# pcb-bldc-servo.net
KiCad netlist of a schematic drawn in EAGLE
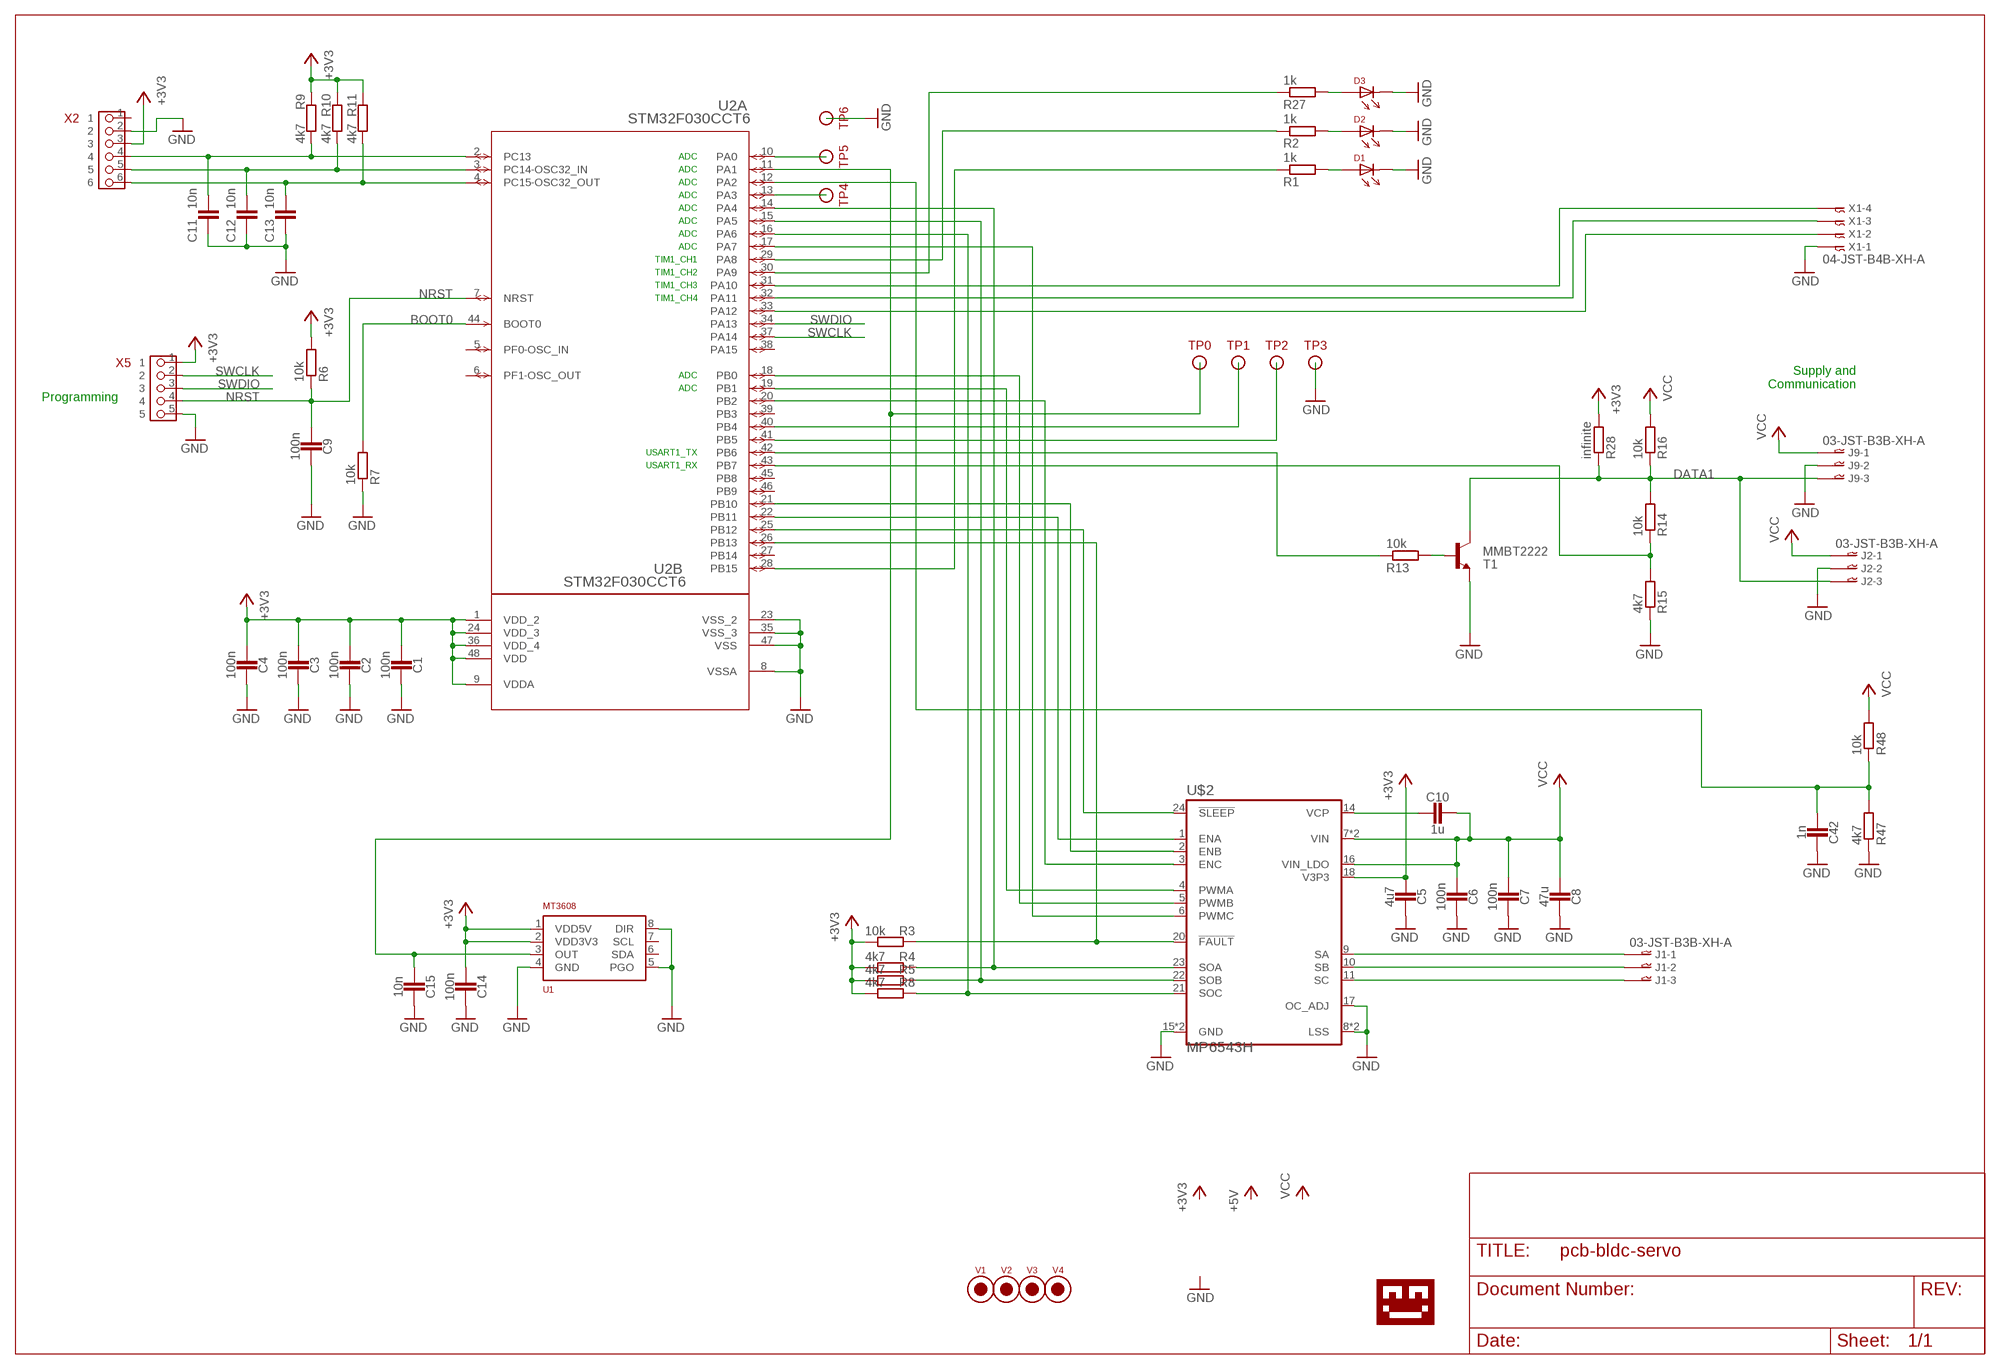
[diagram p0: schematic, sheet 1]

(export (version "E")
  (design (tool "Eeschema 10.0.6"))
  (components
    (comp (ref "C1")
      (value "100n")
      (footprint "eagle-import:0603_CAP")
      (libsource (lib "eagle-import") (part "CAPACITOR0603_CAP"))
    )
    (comp (ref "C2")
      (value "100n")
      (footprint "eagle-import:0603_CAP")
      (libsource (lib "eagle-import") (part "CAPACITOR0603_CAP"))
    )
    (comp (ref "C3")
      (value "100n")
      (footprint "eagle-import:0603_CAP")
      (libsource (lib "eagle-import") (part "CAPACITOR0603_CAP"))
    )
    (comp (ref "C4")
      (value "100n")
      (footprint "eagle-import:0603_CAP")
      (libsource (lib "eagle-import") (part "CAPACITOR0603_CAP"))
    )
    (comp (ref "C5")
      (value "4u7")
      (footprint "eagle-import:0805_CAP")
      (libsource (lib "eagle-import") (part "CAPACITOR0805_CAP"))
    )
    (comp (ref "C6")
      (value "100n")
      (footprint "eagle-import:0603_CAP")
      (libsource (lib "eagle-import") (part "CAPACITOR0603_CAP"))
    )
    (comp (ref "C7")
      (value "100n")
      (footprint "eagle-import:0603_CAP")
      (libsource (lib "eagle-import") (part "CAPACITOR0603_CAP"))
    )
    (comp (ref "C8")
      (value "47u")
      (footprint "eagle-import:1210_CAP")
      (libsource (lib "eagle-import") (part "CAPACITOR1210_CAP"))
    )
    (comp (ref "C9")
      (value "100n")
      (footprint "eagle-import:0603_CAP")
      (libsource (lib "eagle-import") (part "CAPACITOR0603_CAP"))
    )
    (comp (ref "C10")
      (value "1u")
      (footprint "eagle-import:0603_CAP")
      (libsource (lib "eagle-import") (part "CAPACITOR0603_CAP"))
    )
    (comp (ref "C11")
      (value "10n")
      (footprint "eagle-import:0603_CAP")
      (libsource (lib "eagle-import") (part "CAPACITOR0603_CAP"))
    )
    (comp (ref "C12")
      (value "10n")
      (footprint "eagle-import:0603_CAP")
      (libsource (lib "eagle-import") (part "CAPACITOR0603_CAP"))
    )
    (comp (ref "C13")
      (value "10n")
      (footprint "eagle-import:0603_CAP")
      (libsource (lib "eagle-import") (part "CAPACITOR0603_CAP"))
    )
    (comp (ref "C14")
      (value "100n")
      (footprint "eagle-import:0603_CAP")
      (libsource (lib "eagle-import") (part "CAPACITOR0603_CAP"))
    )
    (comp (ref "C15")
      (value "10n")
      (footprint "eagle-import:0603_CAP")
      (libsource (lib "eagle-import") (part "CAPACITOR0603_CAP"))
    )
    (comp (ref "C42")
      (value "1n")
      (footprint "eagle-import:0603_CAP")
      (libsource (lib "eagle-import") (part "CAPACITOR0603_CAP"))
    )
    (comp (ref "D1")
      (value "LED-0805")
      (footprint "eagle-import:0805-DOT")
      (libsource (lib "eagle-import") (part "LED-0805"))
    )
    (comp (ref "D2")
      (value "LED-0805")
      (footprint "eagle-import:0805-DOT")
      (libsource (lib "eagle-import") (part "LED-0805"))
    )
    (comp (ref "D3")
      (value "LED-0805")
      (footprint "eagle-import:0805-DOT")
      (libsource (lib "eagle-import") (part "LED-0805"))
    )
    (comp (ref "J1")
      (value "03-JST-B3B-XH-A")
      (footprint "eagle-import:B3B-XH")
      (libsource (lib "eagle-import") (part "03-JST-B3B-XH-A"))
    )
    (comp (ref "J2")
      (value "03-JST-B3B-XH-A")
      (footprint "eagle-import:B3B-XH")
      (libsource (lib "eagle-import") (part "03-JST-B3B-XH-A"))
    )
    (comp (ref "J9")
      (value "03-JST-B3B-XH-A")
      (footprint "eagle-import:B3B-XH")
      (libsource (lib "eagle-import") (part "03-JST-B3B-XH-A"))
    )
    (comp (ref "R1")
      (value "1k")
      (footprint "eagle-import:0603-RES")
      (libsource (lib "eagle-import") (part "RESISTOR0603_RES"))
    )
    (comp (ref "R2")
      (value "1k")
      (footprint "eagle-import:0603-RES")
      (libsource (lib "eagle-import") (part "RESISTOR0603_RES"))
    )
    (comp (ref "R3")
      (value "10k")
      (footprint "eagle-import:0603-RES")
      (libsource (lib "eagle-import") (part "RESISTOR0603_RES"))
    )
    (comp (ref "R4")
      (value "4k7")
      (footprint "eagle-import:0603-RES")
      (libsource (lib "eagle-import") (part "RESISTOR0603_RES"))
    )
    (comp (ref "R5")
      (value "4k7")
      (footprint "eagle-import:0603-RES")
      (libsource (lib "eagle-import") (part "RESISTOR0603_RES"))
    )
    (comp (ref "R6")
      (value "10k")
      (footprint "eagle-import:0603-RES")
      (libsource (lib "eagle-import") (part "RESISTOR0603_RES"))
    )
    (comp (ref "R7")
      (value "10k")
      (footprint "eagle-import:0603-RES")
      (libsource (lib "eagle-import") (part "RESISTOR0603_RES"))
    )
    (comp (ref "R8")
      (value "4k7")
      (footprint "eagle-import:0603-RES")
      (libsource (lib "eagle-import") (part "RESISTOR0603_RES"))
    )
    (comp (ref "R9")
      (value "4k7")
      (footprint "eagle-import:0603-RES")
      (libsource (lib "eagle-import") (part "RESISTOR0603_RES"))
    )
    (comp (ref "R10")
      (value "4k7")
      (footprint "eagle-import:0603-RES")
      (libsource (lib "eagle-import") (part "RESISTOR0603_RES"))
    )
    (comp (ref "R11")
      (value "4k7")
      (footprint "eagle-import:0603-RES")
      (libsource (lib "eagle-import") (part "RESISTOR0603_RES"))
    )
    (comp (ref "R13")
      (value "10k")
      (footprint "eagle-import:0603-RES")
      (libsource (lib "eagle-import") (part "RESISTOR0603_RES"))
    )
    (comp (ref "R14")
      (value "10k")
      (footprint "eagle-import:0603-RES")
      (libsource (lib "eagle-import") (part "RESISTOR0603_RES"))
    )
    (comp (ref "R15")
      (value "4k7")
      (footprint "eagle-import:0603-RES")
      (libsource (lib "eagle-import") (part "RESISTOR0603_RES"))
    )
    (comp (ref "R16")
      (value "10k")
      (footprint "eagle-import:0603-RES")
      (libsource (lib "eagle-import") (part "RESISTOR0603_RES"))
    )
    (comp (ref "R27")
      (value "1k")
      (footprint "eagle-import:0603-RES")
      (libsource (lib "eagle-import") (part "RESISTOR0603_RES"))
    )
    (comp (ref "R28")
      (value "infinite")
      (footprint "eagle-import:0603-RES")
      (libsource (lib "eagle-import") (part "RESISTOR0603_RES"))
    )
    (comp (ref "R47")
      (value "4k7")
      (footprint "eagle-import:0603-RES")
      (libsource (lib "eagle-import") (part "RESISTOR0603_RES"))
    )
    (comp (ref "R48")
      (value "10k")
      (footprint "eagle-import:0603-RES")
      (libsource (lib "eagle-import") (part "RESISTOR0603_RES"))
    )
    (comp (ref "T1")
      (value "MMBT2222")
      (footprint "eagle-import:SOT23-BEC")
      (libsource (lib "eagle-import") (part "-NPN-SOT23-BECMMBT2222ALT1"))
    )
    (comp (ref "TP0")
      (value "TESTPIN")
      (footprint "eagle-import:PIN-SMD-1X1-TEST_1M5")
      (libsource (lib "eagle-import") (part "TESTPIN"))
    )
    (comp (ref "TP1")
      (value "TESTPIN")
      (footprint "eagle-import:PIN-SMD-1X1-TEST_1M5")
      (libsource (lib "eagle-import") (part "TESTPIN"))
    )
    (comp (ref "TP2")
      (value "TESTPIN")
      (footprint "eagle-import:PIN-SMD-1X1-TEST_1M5")
      (libsource (lib "eagle-import") (part "TESTPIN"))
    )
    (comp (ref "TP3")
      (value "TESTPIN")
      (footprint "eagle-import:PIN-SMD-1X1-TEST_1M5")
      (libsource (lib "eagle-import") (part "TESTPIN"))
    )
    (comp (ref "TP4")
      (value "TESTPIN")
      (footprint "eagle-import:PIN-SMD-1X1-TEST_1M5")
      (libsource (lib "eagle-import") (part "TESTPIN"))
    )
    (comp (ref "TP5")
      (value "TESTPIN")
      (footprint "eagle-import:PIN-SMD-1X1-TEST_1M5")
      (libsource (lib "eagle-import") (part "TESTPIN"))
    )
    (comp (ref "TP6")
      (value "TESTPIN")
      (footprint "eagle-import:PIN-SMD-1X1-TEST_1M5")
      (libsource (lib "eagle-import") (part "TESTPIN"))
    )
    (comp (ref "U$1")
      (value "LOGO-TOBENG-1MM-FINISH")
      (footprint "eagle-import:TOBENG-1MM-FINISH")
      (libsource (lib "eagle-import") (part "LOGO-TOBENG-1MM-FINISH"))
    )
    (comp (ref "U$2")
      (value "MP6543H")
      (footprint "eagle-import:QFN24")
      (libsource (lib "eagle-import") (part "MP6543H"))
    )
    (comp (ref "U1")
      (value "AS5600")
      (footprint "eagle-import:SOIC-8")
      (libsource (lib "eagle-import") (part "AS5600"))
    )
    (comp (ref "U2")
      (value "STM32F030CCT6")
      (footprint "eagle-import:LQFP48-7X7MM")
      (fields (field (name "COPYRIGHT") "Copyright (C) 2018 Accelerated Designs. All rights reserved"))
      (libsource (lib "eagle-import") (part "STM32F030CCT6"))
    )
    (comp (ref "V1")
      (value "FIDUCIAL2MM")
      (footprint "eagle-import:FIDUCIAL_2MM")
      (libsource (lib "eagle-import") (part "FIDUCIAL2MM"))
    )
    (comp (ref "V2")
      (value "FIDUCIAL2MM")
      (footprint "eagle-import:FIDUCIAL_2MM")
      (libsource (lib "eagle-import") (part "FIDUCIAL2MM"))
    )
    (comp (ref "V3")
      (value "FIDUCIAL2MM")
      (footprint "eagle-import:FIDUCIAL_2MM")
      (libsource (lib "eagle-import") (part "FIDUCIAL2MM"))
    )
    (comp (ref "V4")
      (value "FIDUCIAL2MM")
      (footprint "eagle-import:FIDUCIAL_2MM")
      (libsource (lib "eagle-import") (part "FIDUCIAL2MM"))
    )
    (comp (ref "X1")
      (value "04-JST-B4B-XH-A")
      (footprint "eagle-import:B4B-XH")
      (libsource (lib "eagle-import") (part "04-JST-B4B-XH-A"))
    )
    (comp (ref "X2")
      (value "PIN_6X1")
      (footprint "eagle-import:PIN_6X1_MOLEX_PICOBLADE")
      (libsource (lib "eagle-import") (part "PIN_6X1"))
    )
    (comp (ref "X5")
      (value "PIN_5X1HD")
      (footprint "eagle-import:PIN_5X1_HD")
      (libsource (lib "eagle-import") (part "PIN_5X1HD"))
    )
  )
  (nets
    (net (code "1") (name "+3V3") (class "Default")
      (node (ref "C1") (pin "1") (pinfunction "1_1") (pintype "bidirectional"))
      (node (ref "C14") (pin "1") (pinfunction "1_1") (pintype "bidirectional"))
      (node (ref "C2") (pin "1") (pinfunction "1_1") (pintype "bidirectional"))
      (node (ref "C3") (pin "1") (pinfunction "1_1") (pintype "bidirectional"))
      (node (ref "C4") (pin "1") (pinfunction "1_1") (pintype "bidirectional"))
      (node (ref "C5") (pin "P$1") (pinfunction "1_P$1") (pintype "bidirectional"))
      (node (ref "R10") (pin "1") (pinfunction "1_1") (pintype "passive"))
      (node (ref "R11") (pin "1") (pinfunction "1_1") (pintype "passive"))
      (node (ref "R28") (pin "2") (pinfunction "2_2") (pintype "passive"))
      (node (ref "R3") (pin "2") (pinfunction "2_2") (pintype "passive"))
      (node (ref "R4") (pin "2") (pinfunction "2_2") (pintype "passive"))
      (node (ref "R5") (pin "2") (pinfunction "2_2") (pintype "passive"))
      (node (ref "R6") (pin "2") (pinfunction "2_2") (pintype "passive"))
      (node (ref "R8") (pin "2") (pinfunction "2_2") (pintype "passive"))
      (node (ref "R9") (pin "1") (pinfunction "1_1") (pintype "passive"))
      (node (ref "U$2") (pin "18") (pinfunction "V3P3_18") (pintype "bidirectional"))
      (node (ref "U1") (pin "1") (pinfunction "VDD5V_1") (pintype "bidirectional"))
      (node (ref "U1") (pin "2") (pinfunction "VDD3V3_2") (pintype "bidirectional"))
      (node (ref "U2") (pin "1") (pinfunction "VDD_2_1") (pintype "power_in"))
      (node (ref "U2") (pin "24") (pinfunction "VDD_3_24") (pintype "power_in"))
      (node (ref "U2") (pin "36") (pinfunction "VDD_4_36") (pintype "power_in"))
      (node (ref "U2") (pin "48") (pinfunction "VDD_48") (pintype "power_in"))
      (node (ref "U2") (pin "9") (pinfunction "VDDA_9") (pintype "power_in"))
      (node (ref "X2") (pin "3") (pinfunction "3_3") (pintype "bidirectional"))
      (node (ref "X5") (pin "1") (pinfunction "1_1") (pintype "bidirectional"))
    )
    (net (code "3") (name "/BOOT0") (class "Default")
      (node (ref "R7") (pin "2") (pinfunction "2_2") (pintype "passive"))
      (node (ref "U2") (pin "44") (pinfunction "BOOT0_44") (pintype "input"))
    )
    (net (code "4") (name "/DATA1") (class "Default")
      (node (ref "J2") (pin "P$3") (pinfunction "1_P$3") (pintype "passive"))
      (node (ref "J9") (pin "P$3") (pinfunction "1_P$3") (pintype "passive"))
      (node (ref "R14") (pin "2") (pinfunction "2_2") (pintype "passive"))
      (node (ref "R16") (pin "1") (pinfunction "1_1") (pintype "passive"))
      (node (ref "R28") (pin "1") (pinfunction "1_1") (pintype "passive"))
      (node (ref "T1") (pin "C") (pinfunction "C_C") (pintype "passive"))
    )
    (net (code "5") (name "/NRST") (class "Default")
      (node (ref "C9") (pin "1") (pinfunction "1_1") (pintype "bidirectional"))
      (node (ref "R6") (pin "1") (pinfunction "1_1") (pintype "passive"))
      (node (ref "U2") (pin "7") (pinfunction "NRST_7") (pintype "bidirectional"))
      (node (ref "X5") (pin "4") (pinfunction "4_4") (pintype "bidirectional"))
    )
    (net (code "6") (name "/SWCLK") (class "Default")
      (node (ref "U2") (pin "37") (pinfunction "PA14_37") (pintype "bidirectional"))
      (node (ref "X5") (pin "2") (pinfunction "2_2") (pintype "bidirectional"))
    )
    (net (code "7") (name "/SWDIO") (class "Default")
      (node (ref "U2") (pin "34") (pinfunction "PA13_34") (pintype "bidirectional"))
      (node (ref "X5") (pin "3") (pinfunction "3_3") (pintype "bidirectional"))
    )
    (net (code "8") (name "GND") (class "Default")
      (node (ref "C1") (pin "2") (pinfunction "2_2") (pintype "bidirectional"))
      (node (ref "C11") (pin "2") (pinfunction "2_2") (pintype "bidirectional"))
      (node (ref "C12") (pin "2") (pinfunction "2_2") (pintype "bidirectional"))
      (node (ref "C13") (pin "2") (pinfunction "2_2") (pintype "bidirectional"))
      (node (ref "C14") (pin "2") (pinfunction "2_2") (pintype "bidirectional"))
      (node (ref "C15") (pin "2") (pinfunction "2_2") (pintype "bidirectional"))
      (node (ref "C2") (pin "2") (pinfunction "2_2") (pintype "bidirectional"))
      (node (ref "C3") (pin "2") (pinfunction "2_2") (pintype "bidirectional"))
      (node (ref "C4") (pin "2") (pinfunction "2_2") (pintype "bidirectional"))
      (node (ref "C42") (pin "2") (pinfunction "2_2") (pintype "bidirectional"))
      (node (ref "C5") (pin "P$2") (pinfunction "2_P$2") (pintype "bidirectional"))
      (node (ref "C6") (pin "2") (pinfunction "2_2") (pintype "bidirectional"))
      (node (ref "C7") (pin "2") (pinfunction "2_2") (pintype "bidirectional"))
      (node (ref "C8") (pin "2") (pinfunction "2_2") (pintype "bidirectional"))
      (node (ref "C9") (pin "2") (pinfunction "2_2") (pintype "bidirectional"))
      (node (ref "D1") (pin "2") (pinfunction "2_2") (pintype "bidirectional"))
      (node (ref "D2") (pin "2") (pinfunction "2_2") (pintype "bidirectional"))
      (node (ref "D3") (pin "2") (pinfunction "2_2") (pintype "bidirectional"))
      (node (ref "J2") (pin "P$2") (pinfunction "1_P$2") (pintype "passive"))
      (node (ref "J9") (pin "P$2") (pinfunction "1_P$2") (pintype "passive"))
      (node (ref "R15") (pin "1") (pinfunction "1_1") (pintype "passive"))
      (node (ref "R47") (pin "1") (pinfunction "1_1") (pintype "passive"))
      (node (ref "R7") (pin "1") (pinfunction "1_1") (pintype "passive"))
      (node (ref "T1") (pin "E") (pinfunction "E_E") (pintype "passive"))
      (node (ref "TP3") (pin "1") (pinfunction "1_1") (pintype "bidirectional"))
      (node (ref "TP6") (pin "1") (pinfunction "1_1") (pintype "bidirectional"))
      (node (ref "U$2") (pin "12") (pinfunction "LSS_12") (pintype "bidirectional"))
      (node (ref "U$2") (pin "15") (pinfunction "GND_15") (pintype "bidirectional"))
      (node (ref "U$2") (pin "17") (pinfunction "OC_ADJ_17") (pintype "bidirectional"))
      (node (ref "U$2") (pin "25") (pinfunction "GND_25") (pintype "bidirectional"))
      (node (ref "U$2") (pin "8") (pinfunction "LSS_8") (pintype "bidirectional"))
      (node (ref "U1") (pin "4") (pinfunction "GND_4") (pintype "bidirectional"))
      (node (ref "U1") (pin "5") (pinfunction "PGO_5") (pintype "bidirectional"))
      (node (ref "U1") (pin "8") (pinfunction "DIR_8") (pintype "bidirectional"))
      (node (ref "U2") (pin "23") (pinfunction "VSS_2_23") (pintype "power_in"))
      (node (ref "U2") (pin "35") (pinfunction "VSS_3_35") (pintype "power_in"))
      (node (ref "U2") (pin "47") (pinfunction "VSS_47") (pintype "power_in"))
      (node (ref "U2") (pin "8") (pinfunction "VSSA_8") (pintype "power_in"))
      (node (ref "X1") (pin "P$1") (pinfunction "1_P$1") (pintype "passive"))
      (node (ref "X2") (pin "2") (pinfunction "2_2") (pintype "bidirectional"))
      (node (ref "X5") (pin "5") (pinfunction "5_5") (pintype "bidirectional"))
    )
    (net (code "9") (name "Net-(D1-Pad1)") (class "Default")
      (node (ref "D1") (pin "1") (pinfunction "1_1") (pintype "bidirectional"))
      (node (ref "R1") (pin "2") (pinfunction "2_2") (pintype "passive"))
    )
    (net (code "10") (name "Net-(D2-Pad1)") (class "Default")
      (node (ref "D2") (pin "1") (pinfunction "1_1") (pintype "bidirectional"))
      (node (ref "R2") (pin "2") (pinfunction "2_2") (pintype "passive"))
    )
    (net (code "11") (name "Net-(D3-Pad1)") (class "Default")
      (node (ref "D3") (pin "1") (pinfunction "1_1") (pintype "bidirectional"))
      (node (ref "R27") (pin "2") (pinfunction "2_2") (pintype "passive"))
    )
    (net (code "12") (name "Net-(J1A-1)") (class "Default")
      (node (ref "J1") (pin "P$1") (pinfunction "1_P$1") (pintype "passive"))
      (node (ref "U$2") (pin "9") (pinfunction "SA_9") (pintype "bidirectional"))
    )
    (net (code "13") (name "Net-(J1B-1)") (class "Default")
      (node (ref "J1") (pin "P$2") (pinfunction "1_P$2") (pintype "passive"))
      (node (ref "U$2") (pin "10") (pinfunction "SB_10") (pintype "bidirectional"))
    )
    (net (code "14") (name "Net-(J1C-1)") (class "Default")
      (node (ref "J1") (pin "P$3") (pinfunction "1_P$3") (pintype "passive"))
      (node (ref "U$2") (pin "11") (pinfunction "SC_11") (pintype "bidirectional"))
    )
    (net (code "15") (name "Net-(R13-Pad2)") (class "Default")
      (node (ref "R13") (pin "2") (pinfunction "2_2") (pintype "passive"))
      (node (ref "T1") (pin "B") (pinfunction "B_B") (pintype "passive"))
    )
    (net (code "16") (name "Net-(U$2-ENA)") (class "Default")
      (node (ref "U$2") (pin "1") (pinfunction "ENA_1") (pintype "bidirectional"))
      (node (ref "U2") (pin "22") (pinfunction "PB11_22") (pintype "bidirectional"))
    )
    (net (code "17") (name "Net-(U$2-ENB)") (class "Default")
      (node (ref "U$2") (pin "2") (pinfunction "ENB_2") (pintype "bidirectional"))
      (node (ref "U2") (pin "21") (pinfunction "PB10_21") (pintype "bidirectional"))
    )
    (net (code "18") (name "Net-(U$2-ENC)") (class "Default")
      (node (ref "U$2") (pin "3") (pinfunction "ENC_3") (pintype "bidirectional"))
      (node (ref "U2") (pin "20") (pinfunction "PB2_20") (pintype "bidirectional"))
    )
    (net (code "19") (name "Net-(U$2-PWMA)") (class "Default")
      (node (ref "U$2") (pin "4") (pinfunction "PWMA_4") (pintype "bidirectional"))
      (node (ref "U2") (pin "19") (pinfunction "PB1_19") (pintype "bidirectional"))
    )
    (net (code "20") (name "Net-(U$2-PWMB)") (class "Default")
      (node (ref "U$2") (pin "5") (pinfunction "PWMB_5") (pintype "bidirectional"))
      (node (ref "U2") (pin "18") (pinfunction "PB0_18") (pintype "bidirectional"))
    )
    (net (code "21") (name "Net-(U$2-PWMC)") (class "Default")
      (node (ref "U$2") (pin "6") (pinfunction "PWMC_6") (pintype "bidirectional"))
      (node (ref "U2") (pin "17") (pinfunction "PA7_17") (pintype "bidirectional"))
    )
    (net (code "22") (name "Net-(U$2-SOA)") (class "Default")
      (node (ref "R4") (pin "1") (pinfunction "1_1") (pintype "passive"))
      (node (ref "U$2") (pin "23") (pinfunction "SOA_23") (pintype "bidirectional"))
      (node (ref "U2") (pin "14") (pinfunction "PA4_14") (pintype "bidirectional"))
    )
    (net (code "23") (name "Net-(U$2-SOB)") (class "Default")
      (node (ref "R5") (pin "1") (pinfunction "1_1") (pintype "passive"))
      (node (ref "U$2") (pin "22") (pinfunction "SOB_22") (pintype "bidirectional"))
      (node (ref "U2") (pin "15") (pinfunction "PA5_15") (pintype "bidirectional"))
    )
    (net (code "24") (name "Net-(U$2-SOC)") (class "Default")
      (node (ref "R8") (pin "1") (pinfunction "1_1") (pintype "passive"))
      (node (ref "U$2") (pin "21") (pinfunction "SOC_21") (pintype "bidirectional"))
      (node (ref "U2") (pin "16") (pinfunction "PA6_16") (pintype "bidirectional"))
    )
    (net (code "25") (name "Net-(U$2-VCP)") (class "Default")
      (node (ref "C10") (pin "1") (pinfunction "1_1") (pintype "bidirectional"))
      (node (ref "U$2") (pin "14") (pinfunction "VCP_14") (pintype "bidirectional"))
    )
    (net (code "26") (name "Net-(U$2-~{FAULT})") (class "Default")
      (node (ref "R3") (pin "1") (pinfunction "1_1") (pintype "passive"))
      (node (ref "U$2") (pin "20") (pinfunction "~{FAULT}_20") (pintype "bidirectional"))
      (node (ref "U2") (pin "26") (pinfunction "PB13_26") (pintype "bidirectional"))
    )
    (net (code "27") (name "Net-(U$2-~{SLEEP})") (class "Default")
      (node (ref "U$2") (pin "24") (pinfunction "~{SLEEP}_24") (pintype "bidirectional"))
      (node (ref "U2") (pin "25") (pinfunction "PB12_25") (pintype "bidirectional"))
    )
    (net (code "28") (name "Net-(U1-OUT)") (class "Default")
      (node (ref "C15") (pin "1") (pinfunction "1_1") (pintype "bidirectional"))
      (node (ref "TP0") (pin "1") (pinfunction "1_1") (pintype "bidirectional"))
      (node (ref "U1") (pin "3") (pinfunction "OUT_3") (pintype "bidirectional"))
      (node (ref "U2") (pin "11") (pinfunction "PA1_11") (pintype "bidirectional"))
    )
    (net (code "29") (name "Net-(U2A-PA0)") (class "Default")
      (node (ref "TP5") (pin "1") (pinfunction "1_1") (pintype "bidirectional"))
      (node (ref "U2") (pin "10") (pinfunction "PA0_10") (pintype "bidirectional"))
    )
    (net (code "30") (name "Net-(U2A-PA2)") (class "Default")
      (node (ref "C42") (pin "1") (pinfunction "1_1") (pintype "bidirectional"))
      (node (ref "R47") (pin "2") (pinfunction "2_2") (pintype "passive"))
      (node (ref "R48") (pin "1") (pinfunction "1_1") (pintype "passive"))
      (node (ref "U2") (pin "12") (pinfunction "PA2_12") (pintype "bidirectional"))
    )
    (net (code "31") (name "Net-(U2A-PA3)") (class "Default")
      (node (ref "TP4") (pin "1") (pinfunction "1_1") (pintype "bidirectional"))
      (node (ref "U2") (pin "13") (pinfunction "PA3_13") (pintype "bidirectional"))
    )
    (net (code "32") (name "Net-(U2A-PA8)") (class "Default")
      (node (ref "R2") (pin "1") (pinfunction "1_1") (pintype "passive"))
      (node (ref "U2") (pin "29") (pinfunction "PA8_29") (pintype "bidirectional"))
    )
    (net (code "33") (name "Net-(U2A-PA9)") (class "Default")
      (node (ref "R27") (pin "1") (pinfunction "1_1") (pintype "passive"))
      (node (ref "U2") (pin "30") (pinfunction "PA9_30") (pintype "bidirectional"))
    )
    (net (code "34") (name "Net-(U2A-PA10)") (class "Default")
      (node (ref "U2") (pin "31") (pinfunction "PA10_31") (pintype "bidirectional"))
      (node (ref "X1") (pin "P$4") (pinfunction "1_P$4") (pintype "passive"))
    )
    (net (code "35") (name "Net-(U2A-PA11)") (class "Default")
      (node (ref "U2") (pin "32") (pinfunction "PA11_32") (pintype "bidirectional"))
      (node (ref "X1") (pin "P$3") (pinfunction "1_P$3") (pintype "passive"))
    )
    (net (code "36") (name "Net-(U2A-PA12)") (class "Default")
      (node (ref "U2") (pin "33") (pinfunction "PA12_33") (pintype "bidirectional"))
      (node (ref "X1") (pin "P$2") (pinfunction "1_P$2") (pintype "passive"))
    )
    (net (code "37") (name "Net-(U2A-PB4)") (class "Default")
      (node (ref "TP1") (pin "1") (pinfunction "1_1") (pintype "bidirectional"))
      (node (ref "U2") (pin "40") (pinfunction "PB4_40") (pintype "bidirectional"))
    )
    (net (code "38") (name "Net-(U2A-PB5)") (class "Default")
      (node (ref "TP2") (pin "1") (pinfunction "1_1") (pintype "bidirectional"))
      (node (ref "U2") (pin "41") (pinfunction "PB5_41") (pintype "bidirectional"))
    )
    (net (code "39") (name "Net-(U2A-PB6)") (class "Default")
      (node (ref "R13") (pin "1") (pinfunction "1_1") (pintype "passive"))
      (node (ref "U2") (pin "42") (pinfunction "PB6_42") (pintype "bidirectional"))
    )
    (net (code "40") (name "Net-(U2A-PB7)") (class "Default")
      (node (ref "R14") (pin "1") (pinfunction "1_1") (pintype "passive"))
      (node (ref "R15") (pin "2") (pinfunction "2_2") (pintype "passive"))
      (node (ref "U2") (pin "43") (pinfunction "PB7_43") (pintype "bidirectional"))
    )
    (net (code "41") (name "Net-(U2A-PB15)") (class "Default")
      (node (ref "R1") (pin "1") (pinfunction "1_1") (pintype "passive"))
      (node (ref "U2") (pin "28") (pinfunction "PB15_28") (pintype "bidirectional"))
    )
    (net (code "42") (name "Net-(U2A-PC13)") (class "Default")
      (node (ref "C11") (pin "1") (pinfunction "1_1") (pintype "bidirectional"))
      (node (ref "R9") (pin "2") (pinfunction "2_2") (pintype "passive"))
      (node (ref "U2") (pin "2") (pinfunction "PC13_2") (pintype "bidirectional"))
      (node (ref "X2") (pin "4") (pinfunction "4_4") (pintype "bidirectional"))
    )
    (net (code "43") (name "Net-(U2A-PC14-OSC32_IN)") (class "Default")
      (node (ref "C12") (pin "1") (pinfunction "1_1") (pintype "bidirectional"))
      (node (ref "R10") (pin "2") (pinfunction "2_2") (pintype "passive"))
      (node (ref "U2") (pin "3") (pinfunction "PC14-OSC32_IN_3") (pintype "bidirectional"))
      (node (ref "X2") (pin "5") (pinfunction "5_5") (pintype "bidirectional"))
    )
    (net (code "44") (name "Net-(U2A-PC15-OSC32_OUT)") (class "Default")
      (node (ref "C13") (pin "1") (pinfunction "1_1") (pintype "bidirectional"))
      (node (ref "R11") (pin "2") (pinfunction "2_2") (pintype "passive"))
      (node (ref "U2") (pin "4") (pinfunction "PC15-OSC32_OUT_4") (pintype "bidirectional"))
      (node (ref "X2") (pin "6") (pinfunction "6_6") (pintype "bidirectional"))
    )
    (net (code "45") (name "VCC") (class "Default")
      (node (ref "C10") (pin "2") (pinfunction "2_2") (pintype "bidirectional"))
      (node (ref "C6") (pin "1") (pinfunction "1_1") (pintype "bidirectional"))
      (node (ref "C7") (pin "1") (pinfunction "1_1") (pintype "bidirectional"))
      (node (ref "C8") (pin "1") (pinfunction "1_1") (pintype "bidirectional"))
      (node (ref "J2") (pin "P$1") (pinfunction "1_P$1") (pintype "passive"))
      (node (ref "J9") (pin "P$1") (pinfunction "1_P$1") (pintype "passive"))
      (node (ref "R16") (pin "2") (pinfunction "2_2") (pintype "passive"))
      (node (ref "R48") (pin "2") (pinfunction "2_2") (pintype "passive"))
      (node (ref "U$2") (pin "13") (pinfunction "VIN_13") (pintype "bidirectional"))
      (node (ref "U$2") (pin "16") (pinfunction "VIN_LDO_16") (pintype "bidirectional"))
      (node (ref "U$2") (pin "7") (pinfunction "VIN_7") (pintype "bidirectional"))
    )
    (net (code "46") (name "unconnected-(U1-SCL-Pad7)") (class "Default")
      (node (ref "U1") (pin "7") (pinfunction "SCL_7") (pintype "bidirectional"))
    )
    (net (code "47") (name "unconnected-(U1-SDA-Pad6)") (class "Default")
      (node (ref "U1") (pin "6") (pinfunction "SDA_6") (pintype "bidirectional"))
    )
    (net (code "48") (name "unconnected-(U2A-PA15-Pad38)") (class "Default")
      (node (ref "U2") (pin "38") (pinfunction "PA15_38") (pintype "bidirectional"))
    )
    (net (code "49") (name "unconnected-(U2A-PB3-Pad39)") (class "Default")
      (node (ref "U2") (pin "39") (pinfunction "PB3_39") (pintype "bidirectional"))
    )
    (net (code "50") (name "unconnected-(U2A-PB8-Pad45)") (class "Default")
      (node (ref "U2") (pin "45") (pinfunction "PB8_45") (pintype "bidirectional"))
    )
    (net (code "51") (name "unconnected-(U2A-PB9-Pad46)") (class "Default")
      (node (ref "U2") (pin "46") (pinfunction "PB9_46") (pintype "bidirectional"))
    )
    (net (code "52") (name "unconnected-(U2A-PB14-Pad27)") (class "Default")
      (node (ref "U2") (pin "27") (pinfunction "PB14_27") (pintype "bidirectional"))
    )
    (net (code "53") (name "unconnected-(U2A-PF0-OSC_IN-Pad5)") (class "Default")
      (node (ref "U2") (pin "5") (pinfunction "PF0-OSC_IN_5") (pintype "bidirectional"))
    )
    (net (code "54") (name "unconnected-(U2A-PF1-OSC_OUT-Pad6)") (class "Default")
      (node (ref "U2") (pin "6") (pinfunction "PF1-OSC_OUT_6") (pintype "bidirectional"))
    )
    (net (code "55") (name "unconnected-(X2-Pad1)") (class "Default")
      (node (ref "X2") (pin "1") (pinfunction "1_1") (pintype "bidirectional"))
    )
  )
)
